# smallAtmBoard.net
KiCad netlist of a schematic drawn in EAGLE
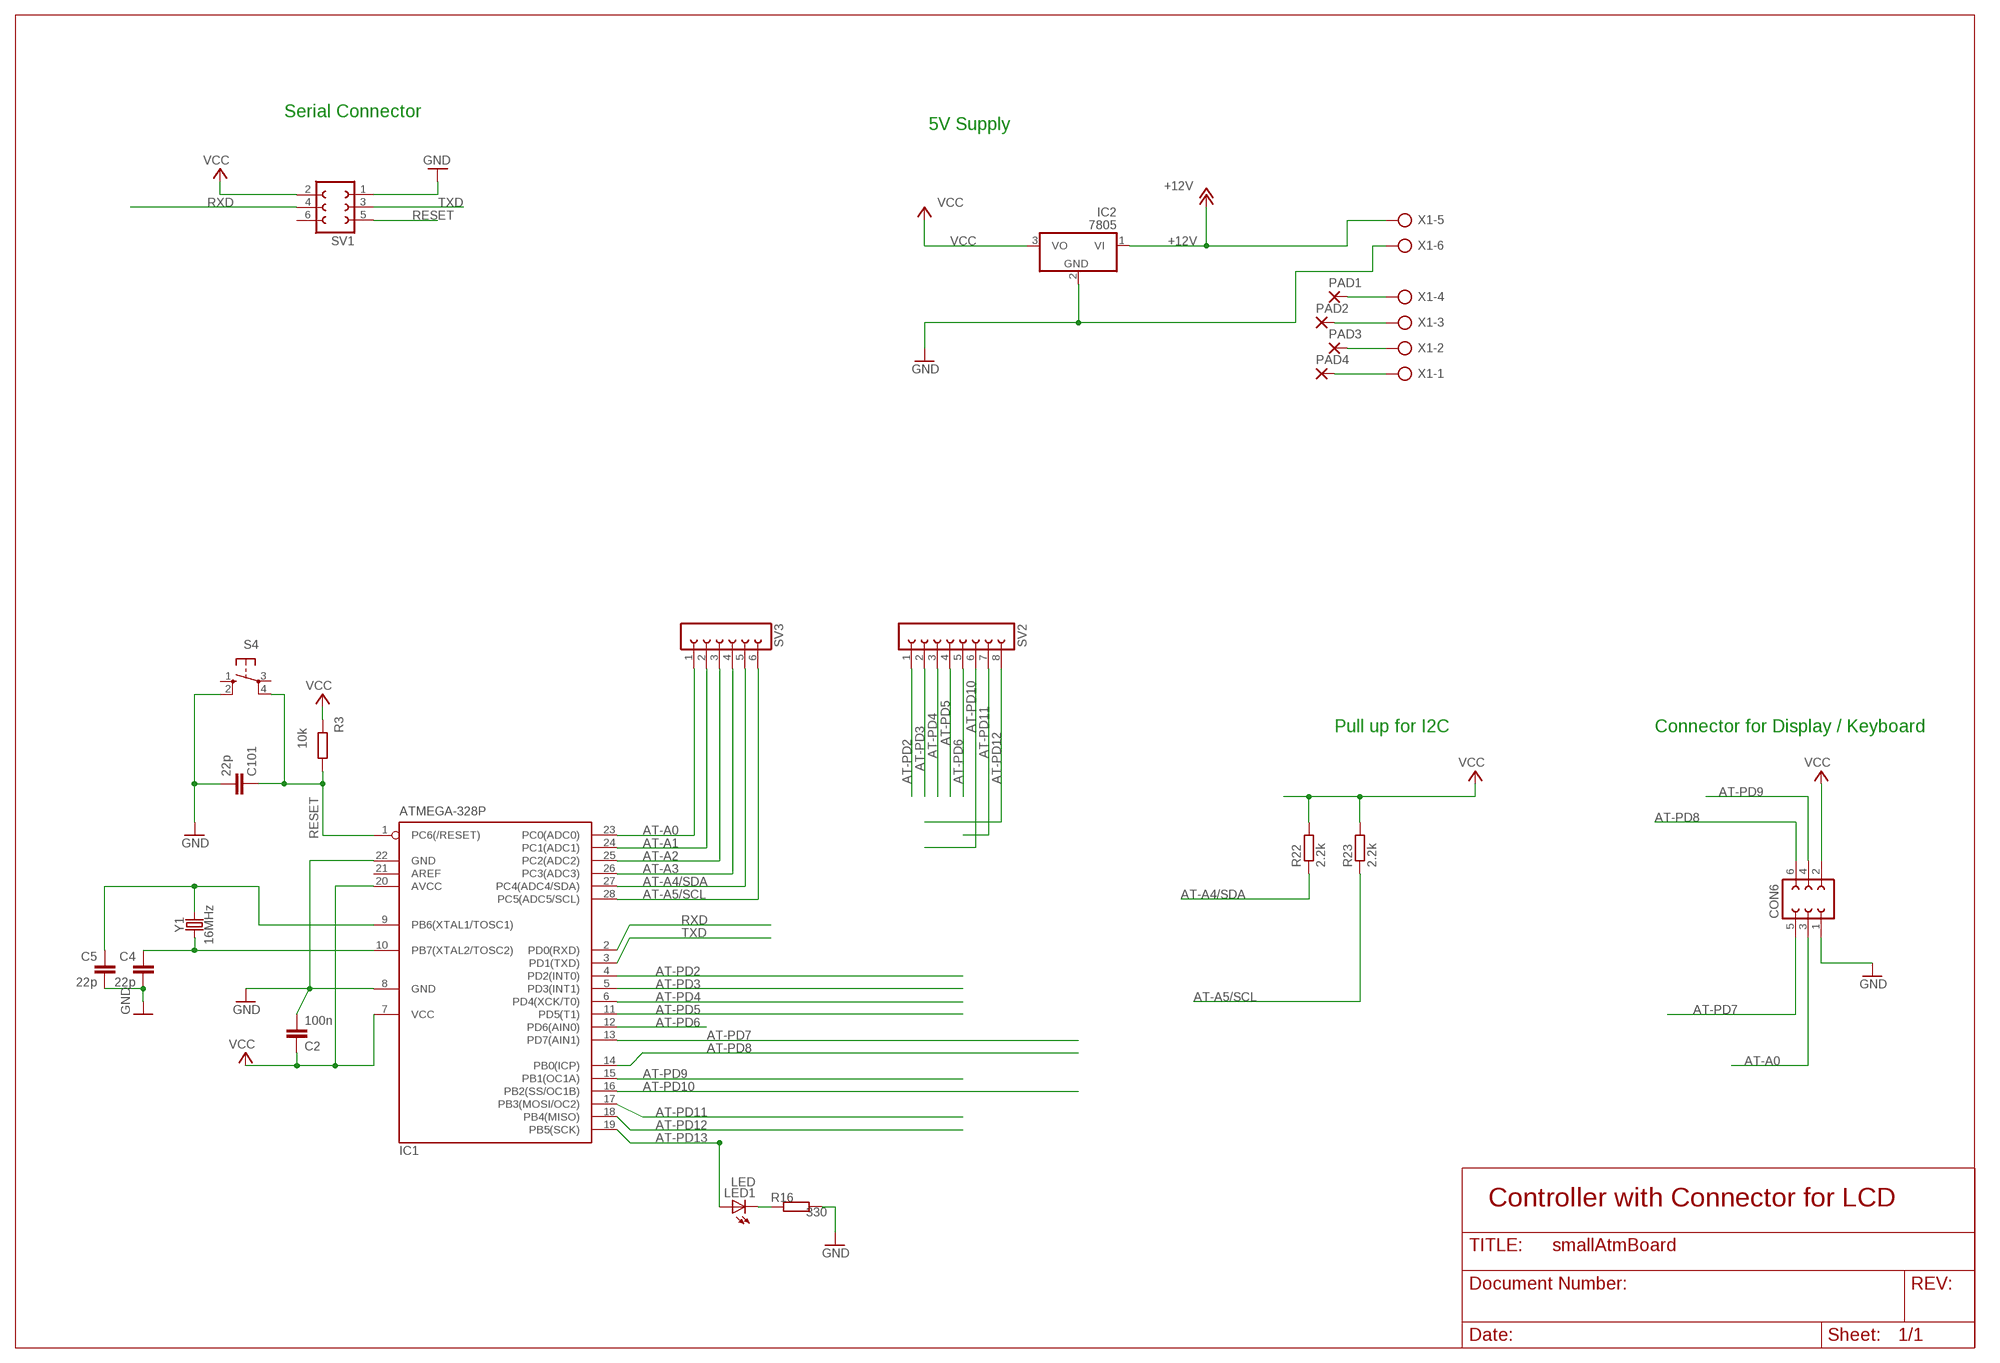
[diagram p0: schematic, sheet 1]

(export (version "E")
  (design (tool "Eeschema 10.0.6"))
  (components
    (comp (ref "C2")
      (value "100n")
      (footprint "eagle-import:C050-024X044")
      (libsource (lib "eagle-import") (part "C-55MM"))
    )
    (comp (ref "C4")
      (value "22p")
      (footprint "eagle-import:C050-024X044")
      (libsource (lib "eagle-import") (part "C-55MM"))
    )
    (comp (ref "C5")
      (value "22p")
      (footprint "eagle-import:C050-024X044")
      (libsource (lib "eagle-import") (part "C-55MM"))
    )
    (comp (ref "C101")
      (value "22p")
      (footprint "eagle-import:C050-024X044")
      (libsource (lib "eagle-import") (part "C-55MM"))
    )
    (comp (ref "CON6")
      (value "FE03-2")
      (footprint "eagle-import:FE03-2")
      (libsource (lib "eagle-import") (part "FE03-2"))
    )
    (comp (ref "IC1")
      (value "ATMEGA-328P")
      (footprint "eagle-import:DIL28-3")
      (libsource (lib "eagle-import") (part "ATMEGA-XX8-P"))
    )
    (comp (ref "IC2")
      (value "7805")
      (footprint "eagle-import:TO220V")
      (libsource (lib "eagle-import") (part "7805-V"))
    )
    (comp (ref "LED1")
      (value "LED")
      (footprint "eagle-import:LED_LD260")
      (libsource (lib "eagle-import") (part "LED"))
    )
    (comp (ref "PAD1")
      (value "PAD1,6/0,8")
      (footprint "eagle-import:PAD1,6_0,8")
      (libsource (lib "eagle-import") (part "PAD1,6/0,8"))
    )
    (comp (ref "PAD2")
      (value "PAD1,6/0,8")
      (footprint "eagle-import:PAD1,6_0,8")
      (libsource (lib "eagle-import") (part "PAD1,6/0,8"))
    )
    (comp (ref "PAD3")
      (value "PAD1,6/0,8")
      (footprint "eagle-import:PAD1,6_0,8")
      (libsource (lib "eagle-import") (part "PAD1,6/0,8"))
    )
    (comp (ref "PAD4")
      (value "PAD1,6/0,8")
      (footprint "eagle-import:PAD1,6_0,8")
      (libsource (lib "eagle-import") (part "PAD1,6/0,8"))
    )
    (comp (ref "R3")
      (value "10k")
      (footprint "eagle-import:R_0207_2V")
      (libsource (lib "eagle-import") (part "R-EU_0207/2V"))
    )
    (comp (ref "R16")
      (value "330")
      (footprint "eagle-import:R_0207_2V")
      (libsource (lib "eagle-import") (part "R-EU_0207/2V"))
    )
    (comp (ref "R22")
      (value "2.2k")
      (footprint "eagle-import:R_0207_2V")
      (libsource (lib "eagle-import") (part "R-EU_0207/2V"))
    )
    (comp (ref "R23")
      (value "2.2k")
      (footprint "eagle-import:R_0207_2V")
      (libsource (lib "eagle-import") (part "R-EU_0207/2V"))
    )
    (comp (ref "S4")
      (value "10-XX")
      (footprint "eagle-import:B3F-10XX")
      (fields (field (name "MPN") "B3F-1000"))
      (libsource (lib "eagle-import") (part "10-XX"))
    )
    (comp (ref "SV1")
      (value "FE03-2FE03-2RAW")
      (footprint "eagle-import:FE03-2RAW")
      (libsource (lib "eagle-import") (part "FE03-2FE03-2RAW"))
    )
    (comp (ref "SV2")
      (value "FE08-1FE08-RAW")
      (footprint "eagle-import:FE08-1-RAW")
      (libsource (lib "eagle-import") (part "FE08-1FE08-RAW"))
    )
    (comp (ref "SV3")
      (value "FE06-1FE06-1-RAW")
      (footprint "eagle-import:FE06-1-RAW")
      (libsource (lib "eagle-import") (part "FE06-1FE06-1-RAW"))
    )
    (comp (ref "X1")
      (value "AK300/6")
      (footprint "eagle-import:AK300_6")
      (libsource (lib "eagle-import") (part "AK300/6"))
    )
    (comp (ref "Y1")
      (value "16MHz")
      (footprint "eagle-import:HC49US")
      (libsource (lib "eagle-import") (part "CRYSTALPTH-HC49US"))
    )
  )
  (nets
    (net (code "1") (name "+12V") (class "Default")
      (node (ref "IC2") (pin "1") (pinfunction "VI_1") (pintype "power_in"))
      (node (ref "X1") (pin "5") (pinfunction "KL_5") (pintype "passive"))
    )
    (net (code "2") (name "/AT-A0") (class "Default")
      (node (ref "CON6") (pin "3") (pinfunction "3_3") (pintype "passive"))
      (node (ref "IC1") (pin "23") (pinfunction "PC0(ADC0)_23") (pintype "bidirectional"))
      (node (ref "SV3") (pin "1") (pinfunction "1_1") (pintype "passive"))
    )
    (net (code "3") (name "/AT-A1") (class "Default")
      (node (ref "IC1") (pin "24") (pinfunction "PC1(ADC1)_24") (pintype "bidirectional"))
      (node (ref "SV3") (pin "2") (pinfunction "2_2") (pintype "passive"))
    )
    (net (code "4") (name "/AT-A2") (class "Default")
      (node (ref "IC1") (pin "25") (pinfunction "PC2(ADC2)_25") (pintype "bidirectional"))
      (node (ref "SV3") (pin "3") (pinfunction "3_3") (pintype "passive"))
    )
    (net (code "5") (name "/AT-A3") (class "Default")
      (node (ref "IC1") (pin "26") (pinfunction "PC3(ADC3)_26") (pintype "bidirectional"))
      (node (ref "SV3") (pin "4") (pinfunction "4_4") (pintype "passive"))
    )
    (net (code "6") (name "/AT-A4{slash}SDA") (class "Default")
      (node (ref "IC1") (pin "27") (pinfunction "PC4(ADC4/SDA)_27") (pintype "bidirectional"))
      (node (ref "R22") (pin "1") (pinfunction "1_1") (pintype "passive"))
      (node (ref "SV3") (pin "5") (pinfunction "5_5") (pintype "passive"))
    )
    (net (code "7") (name "/AT-A5{slash}SCL") (class "Default")
      (node (ref "IC1") (pin "28") (pinfunction "PC5(ADC5/SCL)_28") (pintype "bidirectional"))
      (node (ref "R23") (pin "1") (pinfunction "1_1") (pintype "passive"))
      (node (ref "SV3") (pin "6") (pinfunction "6_6") (pintype "passive"))
    )
    (net (code "8") (name "/AT-PD2") (class "Default")
      (node (ref "IC1") (pin "4") (pinfunction "PD2(INT0)_4") (pintype "bidirectional"))
      (node (ref "SV2") (pin "1") (pinfunction "1_1") (pintype "passive"))
    )
    (net (code "9") (name "/AT-PD3") (class "Default")
      (node (ref "IC1") (pin "5") (pinfunction "PD3(INT1)_5") (pintype "bidirectional"))
      (node (ref "SV2") (pin "2") (pinfunction "2_2") (pintype "passive"))
    )
    (net (code "10") (name "/AT-PD4") (class "Default")
      (node (ref "IC1") (pin "6") (pinfunction "PD4(XCK/T0)_6") (pintype "bidirectional"))
      (node (ref "SV2") (pin "3") (pinfunction "3_3") (pintype "passive"))
    )
    (net (code "11") (name "/AT-PD5") (class "Default")
      (node (ref "IC1") (pin "11") (pinfunction "PD5(T1)_11") (pintype "bidirectional"))
      (node (ref "SV2") (pin "4") (pinfunction "4_4") (pintype "passive"))
    )
    (net (code "12") (name "/AT-PD6") (class "Default")
      (node (ref "IC1") (pin "12") (pinfunction "PD6(AIN0)_12") (pintype "bidirectional"))
      (node (ref "SV2") (pin "5") (pinfunction "5_5") (pintype "passive"))
    )
    (net (code "13") (name "/AT-PD7") (class "Default")
      (node (ref "CON6") (pin "5") (pinfunction "5_5") (pintype "passive"))
      (node (ref "IC1") (pin "13") (pinfunction "PD7(AIN1)_13") (pintype "bidirectional"))
    )
    (net (code "14") (name "/AT-PD8") (class "Default")
      (node (ref "CON6") (pin "6") (pinfunction "6_6") (pintype "passive"))
      (node (ref "IC1") (pin "14") (pinfunction "PB0(ICP)_14") (pintype "bidirectional"))
    )
    (net (code "15") (name "/AT-PD9") (class "Default")
      (node (ref "CON6") (pin "4") (pinfunction "4_4") (pintype "passive"))
      (node (ref "IC1") (pin "15") (pinfunction "PB1(OC1A)_15") (pintype "bidirectional"))
    )
    (net (code "16") (name "/AT-PD10") (class "Default")
      (node (ref "IC1") (pin "16") (pinfunction "PB2(SS/OC1B)_16") (pintype "bidirectional"))
      (node (ref "SV2") (pin "6") (pinfunction "6_6") (pintype "passive"))
    )
    (net (code "17") (name "/AT-PD11") (class "Default")
      (node (ref "IC1") (pin "17") (pinfunction "PB3(MOSI/OC2)_17") (pintype "bidirectional"))
      (node (ref "SV2") (pin "7") (pinfunction "7_7") (pintype "passive"))
    )
    (net (code "18") (name "/AT-PD12") (class "Default")
      (node (ref "IC1") (pin "18") (pinfunction "PB4(MISO)_18") (pintype "bidirectional"))
      (node (ref "SV2") (pin "8") (pinfunction "8_8") (pintype "passive"))
    )
    (net (code "19") (name "/AT-PD13") (class "Default")
      (node (ref "IC1") (pin "19") (pinfunction "PB5(SCK)_19") (pintype "bidirectional"))
      (node (ref "LED1") (pin "A") (pinfunction "A_A") (pintype "passive"))
    )
    (net (code "20") (name "/RESET") (class "Default")
      (node (ref "C101") (pin "1") (pinfunction "1_1") (pintype "passive"))
      (node (ref "IC1") (pin "1") (pinfunction "PC6(/RESET)_1") (pintype "bidirectional"))
      (node (ref "R3") (pin "2") (pinfunction "2_2") (pintype "passive"))
      (node (ref "S4") (pin "4") (pinfunction "P1_4") (pintype "passive"))
      (node (ref "SV1") (pin "5") (pinfunction "5_5") (pintype "passive"))
    )
    (net (code "21") (name "/RXD") (class "Default")
      (node (ref "IC1") (pin "2") (pinfunction "PD0(RXD)_2") (pintype "bidirectional"))
      (node (ref "SV1") (pin "4") (pinfunction "4_4") (pintype "passive"))
    )
    (net (code "22") (name "/TXD") (class "Default")
      (node (ref "IC1") (pin "3") (pinfunction "PD1(TXD)_3") (pintype "bidirectional"))
      (node (ref "SV1") (pin "3") (pinfunction "3_3") (pintype "passive"))
    )
    (net (code "23") (name "GND") (class "Default")
      (node (ref "C101") (pin "2") (pinfunction "2_2") (pintype "passive"))
      (node (ref "C2") (pin "2") (pinfunction "2_2") (pintype "passive"))
      (node (ref "C4") (pin "2") (pinfunction "2_2") (pintype "passive"))
      (node (ref "C5") (pin "2") (pinfunction "2_2") (pintype "passive"))
      (node (ref "CON6") (pin "1") (pinfunction "1_1") (pintype "passive"))
      (node (ref "IC1") (pin "22") (pinfunction "GND_22") (pintype "power_in"))
      (node (ref "IC1") (pin "8") (pinfunction "GND_8") (pintype "power_in"))
      (node (ref "IC2") (pin "2") (pinfunction "GND_2") (pintype "power_in"))
      (node (ref "R16") (pin "1") (pinfunction "1_1") (pintype "passive"))
      (node (ref "S4") (pin "2") (pinfunction "S1_2") (pintype "passive"))
      (node (ref "SV1") (pin "1") (pinfunction "1_1") (pintype "passive"))
      (node (ref "X1") (pin "6") (pinfunction "KL_6") (pintype "passive"))
    )
    (net (code "24") (name "Net-(IC1-PB6(XTAL1{slash}TOSC1))") (class "Default")
      (node (ref "C5") (pin "1") (pinfunction "1_1") (pintype "passive"))
      (node (ref "IC1") (pin "9") (pinfunction "PB6(XTAL1/TOSC1)_9") (pintype "bidirectional"))
      (node (ref "Y1") (pin "2") (pinfunction "2_2") (pintype "passive"))
    )
    (net (code "25") (name "Net-(IC1-PB7(XTAL2{slash}TOSC2))") (class "Default")
      (node (ref "C4") (pin "1") (pinfunction "1_1") (pintype "passive"))
      (node (ref "IC1") (pin "10") (pinfunction "PB7(XTAL2/TOSC2)_10") (pintype "bidirectional"))
      (node (ref "Y1") (pin "1") (pinfunction "1_1") (pintype "passive"))
    )
    (net (code "26") (name "Net-(LED1-C)") (class "Default")
      (node (ref "LED1") (pin "K") (pinfunction "C_K") (pintype "passive"))
      (node (ref "R16") (pin "2") (pinfunction "2_2") (pintype "passive"))
    )
    (net (code "27") (name "Net-(PAD1-P)") (class "Default")
      (node (ref "PAD1") (pin "1") (pinfunction "P_1") (pintype "passive"))
      (node (ref "X1") (pin "4") (pinfunction "KL_4") (pintype "passive"))
    )
    (net (code "28") (name "Net-(PAD2-P)") (class "Default")
      (node (ref "PAD2") (pin "1") (pinfunction "P_1") (pintype "passive"))
      (node (ref "X1") (pin "3") (pinfunction "KL_3") (pintype "passive"))
    )
    (net (code "29") (name "Net-(PAD3-P)") (class "Default")
      (node (ref "PAD3") (pin "1") (pinfunction "P_1") (pintype "passive"))
      (node (ref "X1") (pin "2") (pinfunction "KL_2") (pintype "passive"))
    )
    (net (code "30") (name "Net-(PAD4-P)") (class "Default")
      (node (ref "PAD4") (pin "1") (pinfunction "P_1") (pintype "passive"))
      (node (ref "X1") (pin "1") (pinfunction "KL_1") (pintype "passive"))
    )
    (net (code "31") (name "VCC") (class "Default")
      (node (ref "C2") (pin "1") (pinfunction "1_1") (pintype "passive"))
      (node (ref "CON6") (pin "2") (pinfunction "2_2") (pintype "passive"))
      (node (ref "IC1") (pin "20") (pinfunction "AVCC_20") (pintype "power_in"))
      (node (ref "IC1") (pin "7") (pinfunction "VCC_7") (pintype "power_in"))
      (node (ref "IC2") (pin "3") (pinfunction "VO_3") (pintype "power_in"))
      (node (ref "R22") (pin "2") (pinfunction "2_2") (pintype "passive"))
      (node (ref "R23") (pin "2") (pinfunction "2_2") (pintype "passive"))
      (node (ref "R3") (pin "1") (pinfunction "1_1") (pintype "passive"))
      (node (ref "SV1") (pin "2") (pinfunction "2_2") (pintype "passive"))
    )
    (net (code "32") (name "unconnected-(IC1-AREF-Pad21)") (class "Default")
      (node (ref "IC1") (pin "21") (pinfunction "AREF_21") (pintype "passive"))
    )
    (net (code "33") (name "unconnected-(S4-P-Pad3)") (class "Default")
      (node (ref "S4") (pin "3") (pinfunction "P_3") (pintype "passive"))
    )
    (net (code "34") (name "unconnected-(S4-S-Pad1)") (class "Default")
      (node (ref "S4") (pin "1") (pinfunction "S_1") (pintype "passive"))
    )
    (net (code "35") (name "unconnected-(SV1-Pad6)") (class "Default")
      (node (ref "SV1") (pin "6") (pinfunction "6_6") (pintype "passive"))
    )
  )
)
